# M150.net
KiCad netlist of a schematic drawn in Altium Designer
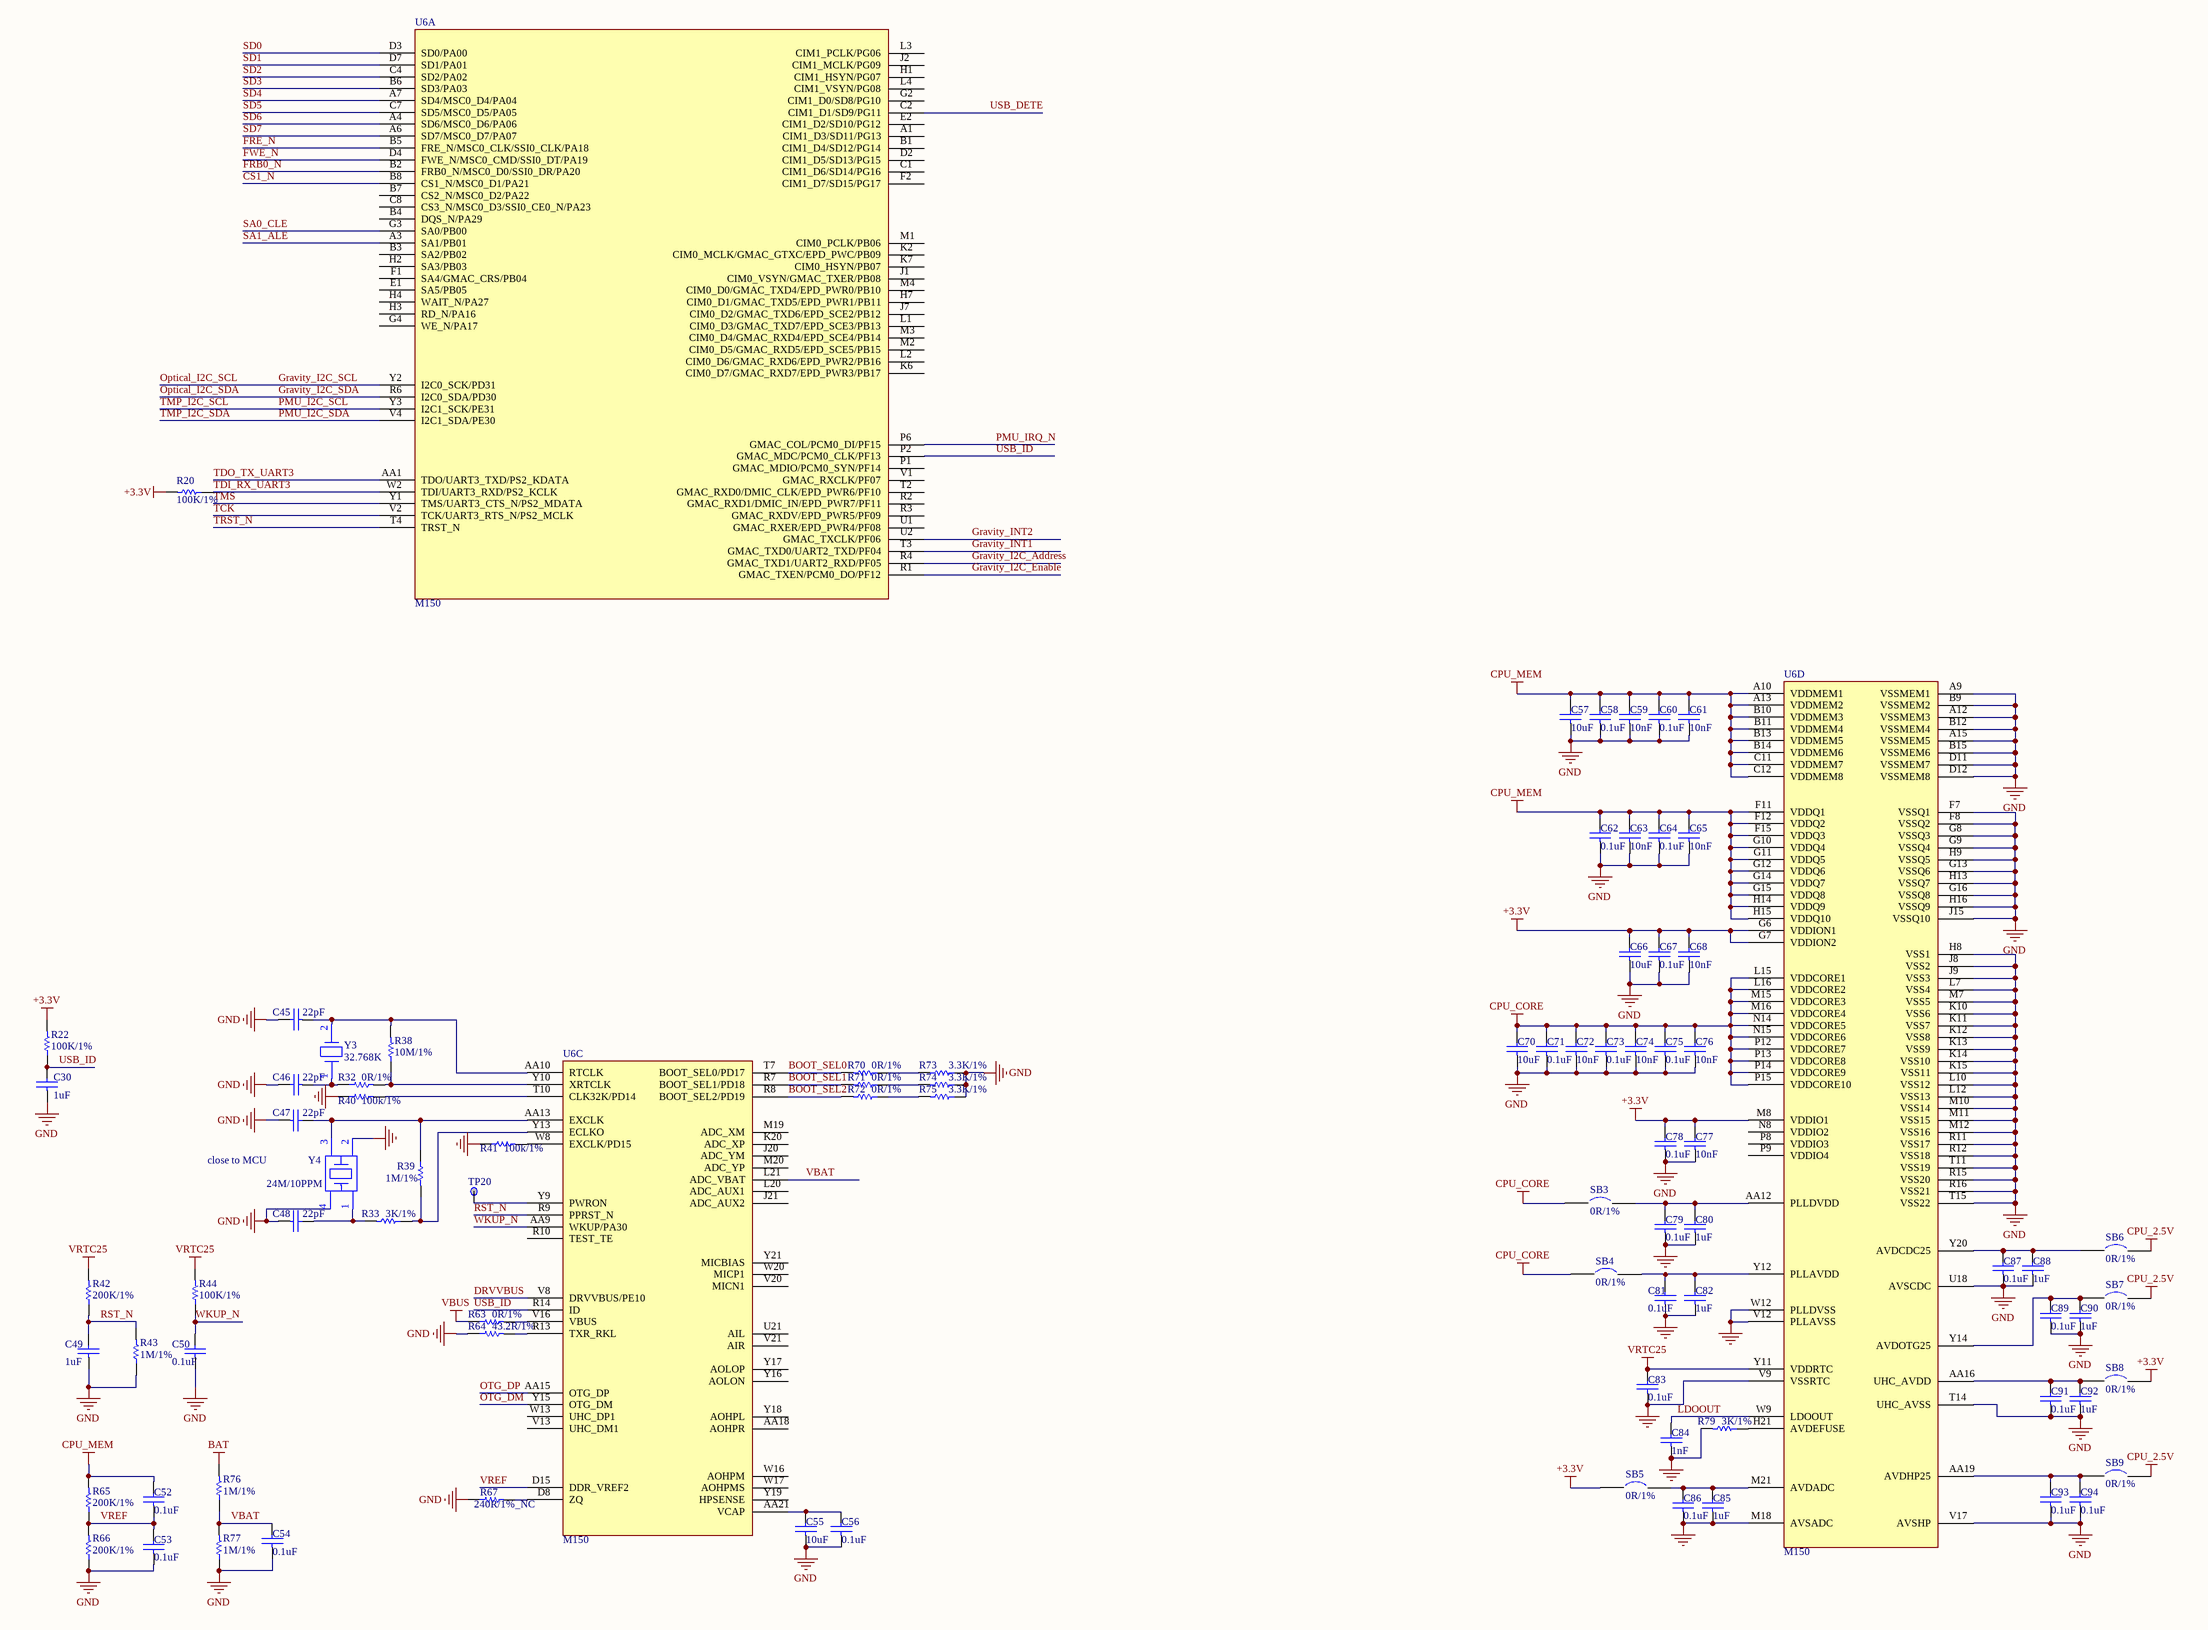
[diagram p0: M150.SchDoc]

(export (version "E")
  (design (tool "Eeschema 10.0.6"))
  (components
    (comp (ref "C30")
      (value "1uF")
      (footprint "0402C")
      (description "厂家：Murata，型号：GRM1555C1H120JA01D")
      (libsource (lib "Amber") (part "CAP"))
    )
    (comp (ref "C45")
      (value "22pF")
      (footprint "0402C")
      (description "Capacitor")
      (libsource (lib "*") (part "CAP"))
    )
    (comp (ref "C46")
      (value "22pF")
      (footprint "0402C")
      (description "Capacitor")
      (libsource (lib "*") (part "CAP"))
    )
    (comp (ref "C47")
      (value "22pF")
      (footprint "0402C")
      (description "厂家：Murata，型号：GRM1555C1H120JA01D")
      (libsource (lib "Amber") (part "CAP"))
    )
    (comp (ref "C48")
      (value "22pF")
      (footprint "0402C")
      (description "厂家：Murata，型号：GRM1555C1H120JA01D")
      (libsource (lib "Amber") (part "CAP"))
    )
    (comp (ref "C49")
      (value "1uF")
      (footprint "0402C")
      (description "厂家：Murata，型号：GRM1555C1H120JA01D")
      (libsource (lib "Amber") (part "CAP"))
    )
    (comp (ref "C50")
      (value "0.1uF")
      (footprint "0402C")
      (description "厂家：Murata，型号：GRM1555C1H120JA01D")
      (libsource (lib "Amber") (part "CAP"))
    )
    (comp (ref "C52")
      (value "0.1uF")
      (footprint "0402C")
      (description "厂家：Murata，型号：GRM1555C1H120JA01D")
      (libsource (lib "Amber") (part "CAP"))
    )
    (comp (ref "C53")
      (value "0.1uF")
      (footprint "0402C")
      (description "厂家：Murata，型号：GRM1555C1H120JA01D")
      (libsource (lib "Amber") (part "CAP"))
    )
    (comp (ref "C54")
      (value "0.1uF")
      (footprint "0402C")
      (description "厂家：Murata，型号：GRM1555C1H120JA01D")
      (libsource (lib "Amber") (part "CAP"))
    )
    (comp (ref "C55")
      (value "10uF")
      (footprint "0402C")
      (description "厂家：Murata，型号：GRM1555C1H120JA01D")
      (libsource (lib "Amber") (part "CAP"))
    )
    (comp (ref "C56")
      (value "0.1uF")
      (footprint "0402C")
      (description "厂家：Murata，型号：GRM1555C1H120JA01D")
      (libsource (lib "Amber") (part "CAP"))
    )
    (comp (ref "C57")
      (value "10uF")
      (footprint "0402C")
      (description "厂家：Murata，型号：GRM1555C1H120JA01D")
      (libsource (lib "Amber") (part "CAP"))
    )
    (comp (ref "C58")
      (value "0.1uF")
      (footprint "0402C")
      (description "厂家：Murata，型号：GRM1555C1H120JA01D")
      (libsource (lib "Amber") (part "CAP"))
    )
    (comp (ref "C59")
      (value "10nF")
      (footprint "0402C")
      (description "厂家：Murata，型号：GRM1555C1H120JA01D")
      (libsource (lib "Amber") (part "CAP"))
    )
    (comp (ref "C60")
      (value "0.1uF")
      (footprint "0402C")
      (description "厂家：Murata，型号：GRM1555C1H120JA01D")
      (libsource (lib "Amber") (part "CAP"))
    )
    (comp (ref "C61")
      (value "10nF")
      (footprint "0402C")
      (description "厂家：Murata，型号：GRM1555C1H120JA01D")
      (libsource (lib "Amber") (part "CAP"))
    )
    (comp (ref "C62")
      (value "0.1uF")
      (footprint "0402C")
      (description "厂家：Murata，型号：GRM1555C1H120JA01D")
      (libsource (lib "Amber") (part "CAP"))
    )
    (comp (ref "C63")
      (value "10nF")
      (footprint "0402C")
      (description "厂家：Murata，型号：GRM1555C1H120JA01D")
      (libsource (lib "Amber") (part "CAP"))
    )
    (comp (ref "C64")
      (value "0.1uF")
      (footprint "0402C")
      (description "厂家：Murata，型号：GRM1555C1H120JA01D")
      (libsource (lib "Amber") (part "CAP"))
    )
    (comp (ref "C65")
      (value "10nF")
      (footprint "0402C")
      (description "厂家：Murata，型号：GRM1555C1H120JA01D")
      (libsource (lib "Amber") (part "CAP"))
    )
    (comp (ref "C66")
      (value "10uF")
      (footprint "0402C")
      (description "厂家：Murata，型号：GRM1555C1H120JA01D")
      (libsource (lib "Amber") (part "CAP"))
    )
    (comp (ref "C67")
      (value "0.1uF")
      (footprint "0402C")
      (description "厂家：Murata，型号：GRM1555C1H120JA01D")
      (libsource (lib "Amber") (part "CAP"))
    )
    (comp (ref "C68")
      (value "10nF")
      (footprint "0402C")
      (description "厂家：Murata，型号：GRM1555C1H120JA01D")
      (libsource (lib "Amber") (part "CAP"))
    )
    (comp (ref "C70")
      (value "10uF")
      (footprint "0402C")
      (description "厂家：Murata，型号：GRM1555C1H120JA01D")
      (libsource (lib "Amber") (part "CAP"))
    )
    (comp (ref "C71")
      (value "0.1uF")
      (footprint "0402C")
      (description "厂家：Murata，型号：GRM1555C1H120JA01D")
      (libsource (lib "Amber") (part "CAP"))
    )
    (comp (ref "C72")
      (value "10nF")
      (footprint "0402C")
      (description "厂家：Murata，型号：GRM1555C1H120JA01D")
      (libsource (lib "Amber") (part "CAP"))
    )
    (comp (ref "C73")
      (value "0.1uF")
      (footprint "0402C")
      (description "厂家：Murata，型号：GRM1555C1H120JA01D")
      (libsource (lib "Amber") (part "CAP"))
    )
    (comp (ref "C74")
      (value "10nF")
      (footprint "0402C")
      (description "厂家：Murata，型号：GRM1555C1H120JA01D")
      (libsource (lib "Amber") (part "CAP"))
    )
    (comp (ref "C75")
      (value "0.1uF")
      (footprint "0402C")
      (description "厂家：Murata，型号：GRM1555C1H120JA01D")
      (libsource (lib "Amber") (part "CAP"))
    )
    (comp (ref "C76")
      (value "10nF")
      (footprint "0402C")
      (description "厂家：Murata，型号：GRM1555C1H120JA01D")
      (libsource (lib "Amber") (part "CAP"))
    )
    (comp (ref "C77")
      (value "10nF")
      (footprint "0402C")
      (description "厂家：Murata，型号：GRM1555C1H120JA01D")
      (libsource (lib "Amber") (part "CAP"))
    )
    (comp (ref "C78")
      (value "0.1uF")
      (footprint "0402C")
      (description "厂家：Murata，型号：GRM1555C1H120JA01D")
      (libsource (lib "Amber") (part "CAP"))
    )
    (comp (ref "C79")
      (value "0.1uF")
      (footprint "0402C")
      (description "厂家：Murata，型号：GRM1555C1H120JA01D")
      (libsource (lib "Amber") (part "CAP"))
    )
    (comp (ref "C80")
      (value "1uF")
      (footprint "0402C")
      (description "厂家：Murata，型号：GRM1555C1H120JA01D")
      (libsource (lib "Amber") (part "CAP"))
    )
    (comp (ref "C81")
      (value "0.1uF")
      (footprint "0402C")
      (description "厂家：Murata，型号：GRM1555C1H120JA01D")
      (libsource (lib "Amber") (part "CAP"))
    )
    (comp (ref "C82")
      (value "1uF")
      (footprint "0402C")
      (description "厂家：Murata，型号：GRM1555C1H120JA01D")
      (libsource (lib "Amber") (part "CAP"))
    )
    (comp (ref "C83")
      (value "0.1uF")
      (footprint "0402C")
      (description "厂家：Murata，型号：GRM1555C1H120JA01D")
      (libsource (lib "Amber") (part "CAP"))
    )
    (comp (ref "C84")
      (value "1nF")
      (footprint "0402C")
      (description "厂家：Murata，型号：GRM1555C1H120JA01D")
      (libsource (lib "Amber") (part "CAP"))
    )
    (comp (ref "C85")
      (value "1uF")
      (footprint "0402C")
      (description "厂家：Murata，型号：GRM1555C1H120JA01D")
      (libsource (lib "Amber") (part "CAP"))
    )
    (comp (ref "C86")
      (value "0.1uF")
      (footprint "0402C")
      (description "厂家：Murata，型号：GRM1555C1H120JA01D")
      (libsource (lib "Amber") (part "CAP"))
    )
    (comp (ref "C87")
      (value "0.1uF")
      (footprint "0402C")
      (description "厂家：Murata，型号：GRM1555C1H120JA01D")
      (libsource (lib "Amber") (part "CAP"))
    )
    (comp (ref "C88")
      (value "1uF")
      (footprint "0402C")
      (description "厂家：Murata，型号：GRM1555C1H120JA01D")
      (libsource (lib "Amber") (part "CAP"))
    )
    (comp (ref "C89")
      (value "0.1uF")
      (footprint "0402C")
      (description "厂家：Murata，型号：GRM1555C1H120JA01D")
      (libsource (lib "Amber") (part "CAP"))
    )
    (comp (ref "C90")
      (value "1uF")
      (footprint "0402C")
      (description "厂家：Murata，型号：GRM1555C1H120JA01D")
      (libsource (lib "Amber") (part "CAP"))
    )
    (comp (ref "C91")
      (value "0.1uF")
      (footprint "0402C")
      (description "厂家：Murata，型号：GRM1555C1H120JA01D")
      (libsource (lib "Amber") (part "CAP"))
    )
    (comp (ref "C92")
      (value "1uF")
      (footprint "0402C")
      (description "厂家：Murata，型号：GRM1555C1H120JA01D")
      (libsource (lib "Amber") (part "CAP"))
    )
    (comp (ref "C93")
      (value "0.1uF")
      (footprint "0402C")
      (description "厂家：Murata，型号：GRM1555C1H120JA01D")
      (libsource (lib "Amber") (part "CAP"))
    )
    (comp (ref "C94")
      (value "0.1uF")
      (footprint "0402C")
      (description "厂家：Murata，型号：GRM1555C1H120JA01D")
      (libsource (lib "Amber") (part "CAP"))
    )
    (comp (ref "R20")
      (value "100K/1%")
      (footprint "0603R")
      (description "Resistor")
      (fields (field (name "PUBLISHER") "Altium Limited"))
      (libsource (lib "Miscellaneous Devices") (part "Res1"))
    )
    (comp (ref "R22")
      (value "100K/1%")
      (footprint "0603R")
      (description "Resistor")
      (fields (field (name "PUBLISHER") "Altium Limited"))
      (libsource (lib "Miscellaneous Devices") (part "Res1"))
    )
    (comp (ref "R32")
      (value "0R/1%")
      (footprint "0603R")
      (description "Resistor")
      (fields (field (name "PUBLISHER") "Altium Limited"))
      (libsource (lib "Miscellaneous Devices") (part "Res1"))
    )
    (comp (ref "R33")
      (value "3K/1%")
      (footprint "0603R")
      (description "Resistor")
      (fields (field (name "PUBLISHER") "Altium Limited"))
      (libsource (lib "") (part "Res1_1"))
    )
    (comp (ref "R38")
      (value "10M/1%")
      (footprint "0603R")
      (description "Resistor")
      (fields (field (name "PUBLISHER") "Altium Limited"))
      (libsource (lib "Miscellaneous Devices") (part "Res1"))
    )
    (comp (ref "R39")
      (value "1M/1%")
      (footprint "0603R")
      (description "Resistor")
      (fields (field (name "PUBLISHER") "Altium Limited"))
      (libsource (lib "") (part "Res1_1"))
    )
    (comp (ref "R40")
      (value "100k/1%")
      (footprint "0603R")
      (description "Resistor")
      (fields (field (name "PUBLISHER") "Altium Limited"))
      (libsource (lib "Miscellaneous Devices") (part "Res1"))
    )
    (comp (ref "R41")
      (value "100k/1%")
      (footprint "0603R")
      (description "Resistor")
      (fields (field (name "PUBLISHER") "Altium Limited"))
      (libsource (lib "Miscellaneous Devices") (part "Res1"))
    )
    (comp (ref "R42")
      (value "200K/1%")
      (footprint "0603R")
      (description "Resistor")
      (fields (field (name "PUBLISHER") "Altium Limited"))
      (libsource (lib "Miscellaneous Devices") (part "Res1"))
    )
    (comp (ref "R43")
      (value "1M/1%")
      (footprint "0603R")
      (description "Resistor")
      (fields (field (name "PUBLISHER") "Altium Limited"))
      (libsource (lib "Miscellaneous Devices") (part "Res1"))
    )
    (comp (ref "R44")
      (value "100K/1%")
      (footprint "0603R")
      (description "Resistor")
      (fields (field (name "PUBLISHER") "Altium Limited"))
      (libsource (lib "Miscellaneous Devices") (part "Res1"))
    )
    (comp (ref "R63")
      (value "0R/1%")
      (footprint "0603R")
      (description "Resistor")
      (fields (field (name "PUBLISHER") "Altium Limited"))
      (libsource (lib "Miscellaneous Devices") (part "Res1"))
    )
    (comp (ref "R64")
      (value "43.2R/1%")
      (footprint "0603R")
      (description "Resistor")
      (fields (field (name "PUBLISHER") "Altium Limited"))
      (libsource (lib "Miscellaneous Devices") (part "Res1"))
    )
    (comp (ref "R65")
      (value "200K/1%")
      (footprint "0603R")
      (description "Resistor")
      (fields (field (name "PUBLISHER") "Altium Limited"))
      (libsource (lib "Miscellaneous Devices") (part "Res1"))
    )
    (comp (ref "R66")
      (value "200K/1%")
      (footprint "0603R")
      (description "Resistor")
      (fields (field (name "PUBLISHER") "Altium Limited"))
      (libsource (lib "Miscellaneous Devices") (part "Res1"))
    )
    (comp (ref "R67")
      (value "240R/1%_NC")
      (footprint "0603R")
      (description "Resistor")
      (fields (field (name "PUBLISHER") "Altium Limited"))
      (libsource (lib "Miscellaneous Devices") (part "Res1"))
    )
    (comp (ref "R70")
      (value "0R/1%")
      (footprint "0603R")
      (description "Resistor")
      (fields (field (name "PUBLISHER") "Altium Limited"))
      (libsource (lib "Miscellaneous Devices") (part "Res1"))
    )
    (comp (ref "R71")
      (value "0R/1%")
      (footprint "0603R")
      (description "Resistor")
      (fields (field (name "PUBLISHER") "Altium Limited"))
      (libsource (lib "Miscellaneous Devices") (part "Res1"))
    )
    (comp (ref "R72")
      (value "0R/1%")
      (footprint "0603R")
      (description "Resistor")
      (fields (field (name "PUBLISHER") "Altium Limited"))
      (libsource (lib "Miscellaneous Devices") (part "Res1"))
    )
    (comp (ref "R73")
      (value "3.3K/1%")
      (footprint "0603R")
      (description "Resistor")
      (fields (field (name "PUBLISHER") "Altium Limited"))
      (libsource (lib "Miscellaneous Devices") (part "Res1"))
    )
    (comp (ref "R74")
      (value "3.3K/1%")
      (footprint "0603R")
      (description "Resistor")
      (fields (field (name "PUBLISHER") "Altium Limited"))
      (libsource (lib "Miscellaneous Devices") (part "Res1"))
    )
    (comp (ref "R75")
      (value "3.3K/1%")
      (footprint "0603R")
      (description "Resistor")
      (fields (field (name "PUBLISHER") "Altium Limited"))
      (libsource (lib "Miscellaneous Devices") (part "Res1"))
    )
    (comp (ref "R76")
      (value "1M/1%")
      (footprint "0603R")
      (description "Resistor")
      (fields (field (name "PUBLISHER") "Altium Limited"))
      (libsource (lib "Miscellaneous Devices") (part "Res1"))
    )
    (comp (ref "R77")
      (value "1M/1%")
      (footprint "0603R")
      (description "Resistor")
      (fields (field (name "PUBLISHER") "Altium Limited"))
      (libsource (lib "Miscellaneous Devices") (part "Res1"))
    )
    (comp (ref "R79")
      (value "3K/1%")
      (footprint "0603R")
      (description "Resistor")
      (fields (field (name "PUBLISHER") "Altium Limited"))
      (libsource (lib "") (part "Res1_1"))
    )
    (comp (ref "SB3")
      (value "0R/1%")
      (footprint "SB_0603")
      (description "Circuit Breaker")
      (fields (field (name "PUBLISHER") "Altium Limited"))
      (libsource (lib "Miscellaneous Devices") (part "Circuit Breaker"))
    )
    (comp (ref "SB4")
      (value "0R/1%")
      (footprint "SB_0603")
      (description "Circuit Breaker")
      (fields (field (name "PUBLISHER") "Altium Limited"))
      (libsource (lib "Miscellaneous Devices") (part "Circuit Breaker"))
    )
    (comp (ref "SB5")
      (value "0R/1%")
      (footprint "SB_0603")
      (description "Circuit Breaker")
      (fields (field (name "PUBLISHER") "Altium Limited"))
      (libsource (lib "Miscellaneous Devices") (part "Circuit Breaker"))
    )
    (comp (ref "SB6")
      (value "0R/1%")
      (footprint "SB_0603")
      (description "Circuit Breaker")
      (fields (field (name "PUBLISHER") "Altium Limited"))
      (libsource (lib "Miscellaneous Devices") (part "Circuit Breaker"))
    )
    (comp (ref "SB7")
      (value "0R/1%")
      (footprint "SB_0603")
      (description "Circuit Breaker")
      (fields (field (name "PUBLISHER") "Altium Limited"))
      (libsource (lib "Miscellaneous Devices") (part "Circuit Breaker"))
    )
    (comp (ref "SB8")
      (value "0R/1%")
      (footprint "SB_0603")
      (description "Circuit Breaker")
      (fields (field (name "PUBLISHER") "Altium Limited"))
      (libsource (lib "Miscellaneous Devices") (part "Circuit Breaker"))
    )
    (comp (ref "SB9")
      (value "0R/1%")
      (footprint "SB_0603")
      (description "Circuit Breaker")
      (fields (field (name "PUBLISHER") "Altium Limited"))
      (libsource (lib "Miscellaneous Devices") (part "Circuit Breaker"))
    )
    (comp (ref "TP20") (value "TP") (footprint "TP_C40") (libsource (lib "Almos") (part "TP")))
    (comp (ref "U6") (value "M150") (footprint "Model Name") (libsource (lib "M150") (part "M150")))
    (comp (ref "Y3")
      (value "32.768K")
      (footprint "XTALSMD2-3215")
      (description "厂家：EPSON，型号：Q13FC1350000400")
      (libsource (lib "Amber") (part "CRYSTAL3"))
    )
    (comp (ref "Y4")
      (value "24M/10PPM")
      (footprint "XTALSMD2-2520")
      (description "厂家：EPSON，型号：Q24FA20H0004400")
      (libsource (lib "Amber_1") (part "CRYSTAL2"))
    )
  )
  (nets
    (net (code "1") (name "+3.3V") (class "Default")
      (node (ref "C66") (pin "2") (pinfunction "2_2") (pintype "passive"))
      (node (ref "C67") (pin "2") (pinfunction "2_2") (pintype "passive"))
      (node (ref "C68") (pin "2") (pinfunction "2_2") (pintype "passive"))
      (node (ref "C77") (pin "2") (pinfunction "2_2") (pintype "passive"))
      (node (ref "C78") (pin "2") (pinfunction "2_2") (pintype "passive"))
      (node (ref "R20") (pin "2") (pinfunction "2_2") (pintype "passive"))
      (node (ref "R22") (pin "2") (pinfunction "2_2") (pintype "passive"))
      (node (ref "SB5") (pin "1") (pinfunction "1_1") (pintype "passive"))
      (node (ref "SB8") (pin "2") (pinfunction "2_2") (pintype "passive"))
      (node (ref "U6") (pin "G6") (pinfunction "VDDION1_G6") (pintype "passive"))
      (node (ref "U6") (pin "G7") (pinfunction "VDDION2_G7") (pintype "passive"))
      (node (ref "U6") (pin "M8") (pinfunction "VDDIO1_M8") (pintype "passive"))
    )
    (net (code "2") (name "/BOOT_SEL0") (class "Default")
      (node (ref "R70") (pin "2") (pinfunction "2_2") (pintype "passive"))
      (node (ref "U6") (pin "T7") (pinfunction "BOOT_SEL0/PD17_T7") (pintype "passive"))
    )
    (net (code "3") (name "/BOOT_SEL1") (class "Default")
      (node (ref "R71") (pin "2") (pinfunction "2_2") (pintype "passive"))
      (node (ref "U6") (pin "R7") (pinfunction "BOOT_SEL1/PD18_R7") (pintype "passive"))
    )
    (net (code "4") (name "/BOOT_SEL2") (class "Default")
      (node (ref "R72") (pin "2") (pinfunction "2_2") (pintype "passive"))
      (node (ref "U6") (pin "R8") (pinfunction "BOOT_SEL2/PD19_R8") (pintype "passive"))
    )
    (net (code "5") (name "/CS1_N") (class "Default")
      (node (ref "U6") (pin "B8") (pinfunction "CS1_N/MSC0_D1/PA21_B8") (pintype "passive"))
    )
    (net (code "6") (name "/DRVVBUS") (class "Default")
      (node (ref "U6") (pin "V8") (pinfunction "DRVVBUS/PE10_V8") (pintype "passive"))
    )
    (net (code "7") (name "/FRB0_N") (class "Default")
      (node (ref "U6") (pin "B2") (pinfunction "FRB0_N/MSC0_D0/SSI0_DR/PA20_B2") (pintype "passive"))
    )
    (net (code "8") (name "/FRE_N") (class "Default")
      (node (ref "U6") (pin "B5") (pinfunction "FRE_N/MSC0_CLK/SSI0_CLK/PA18_B5") (pintype "passive"))
    )
    (net (code "9") (name "/FWE_N") (class "Default")
      (node (ref "U6") (pin "D4") (pinfunction "FWE_N/MSC0_CMD/SSI0_DT/PA19_D4") (pintype "passive"))
    )
    (net (code "10") (name "/Gravity_I2C_Address") (class "Default")
      (node (ref "U6") (pin "R4") (pinfunction "GMAC_TXD1/UART2_RXD/PF05_R4") (pintype "passive"))
    )
    (net (code "11") (name "/Gravity_I2C_Enable") (class "Default")
      (node (ref "U6") (pin "R1") (pinfunction "GMAC_TXEN/PCM0_DO/PF12_R1") (pintype "passive"))
    )
    (net (code "12") (name "/Gravity_I2C_SCL") (class "Default")
      (node (ref "U6") (pin "Y2") (pinfunction "I2C0_SCK/PD31_Y2") (pintype "passive"))
    )
    (net (code "13") (name "/Gravity_I2C_SDA") (class "Default")
      (node (ref "U6") (pin "R6") (pinfunction "I2C0_SDA/PD30_R6") (pintype "passive"))
    )
    (net (code "14") (name "/Gravity_INT1") (class "Default")
      (node (ref "U6") (pin "T3") (pinfunction "GMAC_TXD0/UART2_TXD/PF04_T3") (pintype "passive"))
    )
    (net (code "15") (name "/Gravity_INT2") (class "Default")
      (node (ref "U6") (pin "U2") (pinfunction "GMAC_TXCLK/PF06_U2") (pintype "passive"))
    )
    (net (code "16") (name "/LDOOUT") (class "Default")
      (node (ref "C84") (pin "2") (pinfunction "2_2") (pintype "passive"))
      (node (ref "U6") (pin "W9") (pinfunction "LDOOUT_W9") (pintype "passive"))
    )
    (net (code "17") (name "/OTG_DM") (class "Default")
      (node (ref "U6") (pin "Y15") (pinfunction "OTG_DM_Y15") (pintype "passive"))
    )
    (net (code "18") (name "/OTG_DP") (class "Default")
      (node (ref "U6") (pin "AA15") (pinfunction "OTG_DP_AA15") (pintype "passive"))
    )
    (net (code "19") (name "/PMU_I2C_SCL") (class "Default")
      (node (ref "U6") (pin "Y3") (pinfunction "I2C1_SCK/PE31_Y3") (pintype "passive"))
    )
    (net (code "20") (name "/PMU_I2C_SDA") (class "Default")
      (node (ref "U6") (pin "V4") (pinfunction "I2C1_SDA/PE30_V4") (pintype "passive"))
    )
    (net (code "21") (name "/PMU_IRQ_N") (class "Default")
      (node (ref "U6") (pin "P6") (pinfunction "GMAC_COL/PCM0_DI/PF15_P6") (pintype "passive"))
    )
    (net (code "22") (name "/RST_N") (class "Default")
      (node (ref "C49") (pin "2") (pinfunction "2_2") (pintype "passive"))
      (node (ref "R42") (pin "1") (pinfunction "1_1") (pintype "passive"))
      (node (ref "R43") (pin "2") (pinfunction "2_2") (pintype "passive"))
      (node (ref "U6") (pin "R9") (pinfunction "PPRST_N_R9") (pintype "passive"))
    )
    (net (code "23") (name "/SA0_CLE") (class "Default")
      (node (ref "U6") (pin "G3") (pinfunction "SA0/PB00_G3") (pintype "passive"))
    )
    (net (code "24") (name "/SA1_ALE") (class "Default")
      (node (ref "U6") (pin "A3") (pinfunction "SA1/PB01_A3") (pintype "passive"))
    )
    (net (code "25") (name "/SD0") (class "Default")
      (node (ref "U6") (pin "D3") (pinfunction "SD0/PA00_D3") (pintype "passive"))
    )
    (net (code "26") (name "/SD1") (class "Default")
      (node (ref "U6") (pin "D7") (pinfunction "SD1/PA01_D7") (pintype "passive"))
    )
    (net (code "27") (name "/SD2") (class "Default")
      (node (ref "U6") (pin "C4") (pinfunction "SD2/PA02_C4") (pintype "passive"))
    )
    (net (code "28") (name "/SD3") (class "Default")
      (node (ref "U6") (pin "B6") (pinfunction "SD3/PA03_B6") (pintype "passive"))
    )
    (net (code "29") (name "/SD4") (class "Default")
      (node (ref "U6") (pin "A7") (pinfunction "SD4/MSC0_D4/PA04_A7") (pintype "passive"))
    )
    (net (code "30") (name "/SD5") (class "Default")
      (node (ref "U6") (pin "C7") (pinfunction "SD5/MSC0_D5/PA05_C7") (pintype "passive"))
    )
    (net (code "31") (name "/SD6") (class "Default")
      (node (ref "U6") (pin "A4") (pinfunction "SD6/MSC0_D6/PA06_A4") (pintype "passive"))
    )
    (net (code "32") (name "/SD7") (class "Default")
      (node (ref "U6") (pin "A6") (pinfunction "SD7/MSC0_D7/PA07_A6") (pintype "passive"))
    )
    (net (code "33") (name "/TCK") (class "Default")
      (node (ref "U6") (pin "V2") (pinfunction "TCK/UART3_RTS_N/PS2_MCLK_V2") (pintype "passive"))
    )
    (net (code "34") (name "/TDI_RX_UART3") (class "Default")
      (node (ref "R20") (pin "1") (pinfunction "1_1") (pintype "passive"))
      (node (ref "U6") (pin "W2") (pinfunction "TDI/UART3_RXD/PS2_KCLK_W2") (pintype "passive"))
    )
    (net (code "35") (name "/TDO_TX_UART3") (class "Default")
      (node (ref "U6") (pin "AA1") (pinfunction "TDO/UART3_TXD/PS2_KDATA_AA1") (pintype "passive"))
    )
    (net (code "36") (name "/TMS") (class "Default")
      (node (ref "U6") (pin "Y1") (pinfunction "TMS/UART3_CTS_N/PS2_MDATA_Y1") (pintype "passive"))
    )
    (net (code "37") (name "/TRST_N") (class "Default")
      (node (ref "U6") (pin "T4") (pinfunction "TRST_N_T4") (pintype "passive"))
    )
    (net (code "38") (name "/USB_DETE") (class "Default")
      (node (ref "U6") (pin "C2") (pinfunction "CIM1_D1/SD9/PG11_C2") (pintype "passive"))
    )
    (net (code "39") (name "/USB_ID") (class "Default")
      (node (ref "C30") (pin "2") (pinfunction "2_2") (pintype "passive"))
      (node (ref "R22") (pin "1") (pinfunction "1_1") (pintype "passive"))
      (node (ref "U6") (pin "P2") (pinfunction "GMAC_MDC/PCM0_CLK/PF13_P2") (pintype "passive"))
      (node (ref "U6") (pin "R14") (pinfunction "ID_R14") (pintype "passive"))
    )
    (net (code "40") (name "/VBAT") (class "Default")
      (node (ref "C54") (pin "2") (pinfunction "2_2") (pintype "passive"))
      (node (ref "R76") (pin "1") (pinfunction "1_1") (pintype "passive"))
      (node (ref "R77") (pin "2") (pinfunction "2_2") (pintype "passive"))
      (node (ref "U6") (pin "L21") (pinfunction "ADC_VBAT_L21") (pintype "passive"))
    )
    (net (code "41") (name "/VREF") (class "Default")
      (node (ref "C52") (pin "1") (pinfunction "1_1") (pintype "passive"))
      (node (ref "C53") (pin "2") (pinfunction "2_2") (pintype "passive"))
      (node (ref "R65") (pin "1") (pinfunction "1_1") (pintype "passive"))
      (node (ref "R66") (pin "2") (pinfunction "2_2") (pintype "passive"))
      (node (ref "U6") (pin "D15") (pinfunction "DDR_VREF2_D15") (pintype "passive"))
    )
    (net (code "42") (name "/WKUP_N") (class "Default")
      (node (ref "C50") (pin "2") (pinfunction "2_2") (pintype "passive"))
      (node (ref "R44") (pin "1") (pinfunction "1_1") (pintype "passive"))
      (node (ref "U6") (pin "AA9") (pinfunction "WKUP/PA30_AA9") (pintype "passive"))
    )
    (net (code "43") (name "BAT") (class "Default")
      (node (ref "R76") (pin "2") (pinfunction "2_2") (pintype "passive"))
    )
    (net (code "44") (name "CPU_2.5V") (class "Default")
      (node (ref "SB6") (pin "2") (pinfunction "2_2") (pintype "passive"))
      (node (ref "SB7") (pin "2") (pinfunction "2_2") (pintype "passive"))
      (node (ref "SB9") (pin "2") (pinfunction "2_2") (pintype "passive"))
    )
    (net (code "45") (name "CPU_CORE") (class "Default")
      (node (ref "C70") (pin "2") (pinfunction "2_2") (pintype "passive"))
      (node (ref "C71") (pin "2") (pinfunction "2_2") (pintype "passive"))
      (node (ref "C72") (pin "2") (pinfunction "2_2") (pintype "passive"))
      (node (ref "C73") (pin "2") (pinfunction "2_2") (pintype "passive"))
      (node (ref "C74") (pin "2") (pinfunction "2_2") (pintype "passive"))
      (node (ref "C75") (pin "2") (pinfunction "2_2") (pintype "passive"))
      (node (ref "C76") (pin "2") (pinfunction "2_2") (pintype "passive"))
      (node (ref "SB3") (pin "1") (pinfunction "1_1") (pintype "passive"))
      (node (ref "SB4") (pin "1") (pinfunction "1_1") (pintype "passive"))
      (node (ref "U6") (pin "L15") (pinfunction "VDDCORE1_L15") (pintype "passive"))
      (node (ref "U6") (pin "L16") (pinfunction "VDDCORE2_L16") (pintype "passive"))
      (node (ref "U6") (pin "M15") (pinfunction "VDDCORE3_M15") (pintype "passive"))
      (node (ref "U6") (pin "M16") (pinfunction "VDDCORE4_M16") (pintype "passive"))
      (node (ref "U6") (pin "N14") (pinfunction "VDDCORE5_N14") (pintype "passive"))
      (node (ref "U6") (pin "N15") (pinfunction "VDDCORE6_N15") (pintype "passive"))
      (node (ref "U6") (pin "P12") (pinfunction "VDDCORE7_P12") (pintype "passive"))
      (node (ref "U6") (pin "P13") (pinfunction "VDDCORE8_P13") (pintype "passive"))
      (node (ref "U6") (pin "P14") (pinfunction "VDDCORE9_P14") (pintype "passive"))
      (node (ref "U6") (pin "P15") (pinfunction "VDDCORE10_P15") (pintype "passive"))
    )
    (net (code "46") (name "CPU_MEM") (class "Default")
      (node (ref "C52") (pin "2") (pinfunction "2_2") (pintype "passive"))
      (node (ref "C57") (pin "2") (pinfunction "2_2") (pintype "passive"))
      (node (ref "C58") (pin "2") (pinfunction "2_2") (pintype "passive"))
      (node (ref "C59") (pin "2") (pinfunction "2_2") (pintype "passive"))
      (node (ref "C60") (pin "2") (pinfunction "2_2") (pintype "passive"))
      (node (ref "C61") (pin "2") (pinfunction "2_2") (pintype "passive"))
      (node (ref "C62") (pin "2") (pinfunction "2_2") (pintype "passive"))
      (node (ref "C63") (pin "2") (pinfunction "2_2") (pintype "passive"))
      (node (ref "C64") (pin "2") (pinfunction "2_2") (pintype "passive"))
      (node (ref "C65") (pin "2") (pinfunction "2_2") (pintype "passive"))
      (node (ref "R65") (pin "2") (pinfunction "2_2") (pintype "passive"))
      (node (ref "U6") (pin "A10") (pinfunction "VDDMEM1_A10") (pintype "passive"))
      (node (ref "U6") (pin "A13") (pinfunction "VDDMEM2_A13") (pintype "passive"))
      (node (ref "U6") (pin "B10") (pinfunction "VDDMEM3_B10") (pintype "passive"))
      (node (ref "U6") (pin "B11") (pinfunction "VDDMEM4_B11") (pintype "passive"))
      (node (ref "U6") (pin "B13") (pinfunction "VDDMEM5_B13") (pintype "passive"))
      (node (ref "U6") (pin "B14") (pinfunction "VDDMEM6_B14") (pintype "passive"))
      (node (ref "U6") (pin "C11") (pinfunction "VDDMEM7_C11") (pintype "passive"))
      (node (ref "U6") (pin "C12") (pinfunction "VDDMEM8_C12") (pintype "passive"))
      (node (ref "U6") (pin "F11") (pinfunction "VDDQ1_F11") (pintype "passive"))
      (node (ref "U6") (pin "F12") (pinfunction "VDDQ2_F12") (pintype "passive"))
      (node (ref "U6") (pin "F15") (pinfunction "VDDQ3_F15") (pintype "passive"))
      (node (ref "U6") (pin "G10") (pinfunction "VDDQ4_G10") (pintype "passive"))
      (node (ref "U6") (pin "G11") (pinfunction "VDDQ5_G11") (pintype "passive"))
      (node (ref "U6") (pin "G12") (pinfunction "VDDQ6_G12") (pintype "passive"))
      (node (ref "U6") (pin "G14") (pinfunction "VDDQ7_G14") (pintype "passive"))
      (node (ref "U6") (pin "G15") (pinfunction "VDDQ8_G15") (pintype "passive"))
      (node (ref "U6") (pin "H14") (pinfunction "VDDQ9_H14") (pintype "passive"))
      (node (ref "U6") (pin "H15") (pinfunction "VDDQ10_H15") (pintype "passive"))
    )
    (net (code "47") (name "GND") (class "Default")
      (node (ref "C30") (pin "1") (pinfunction "1_1") (pintype "passive"))
      (node (ref "C45") (pin "2") (pinfunction "2_2") (pintype "passive"))
      (node (ref "C46") (pin "2") (pinfunction "2_2") (pintype "passive"))
      (node (ref "C47") (pin "1") (pinfunction "1_1") (pintype "passive"))
      (node (ref "C48") (pin "1") (pinfunction "1_1") (pintype "passive"))
      (node (ref "C49") (pin "1") (pinfunction "1_1") (pintype "passive"))
      (node (ref "C50") (pin "1") (pinfunction "1_1") (pintype "passive"))
      (node (ref "C53") (pin "1") (pinfunction "1_1") (pintype "passive"))
      (node (ref "C54") (pin "1") (pinfunction "1_1") (pintype "passive"))
      (node (ref "C55") (pin "1") (pinfunction "1_1") (pintype "passive"))
      (node (ref "C56") (pin "1") (pinfunction "1_1") (pintype "passive"))
      (node (ref "C57") (pin "1") (pinfunction "1_1") (pintype "passive"))
      (node (ref "C58") (pin "1") (pinfunction "1_1") (pintype "passive"))
      (node (ref "C59") (pin "1") (pinfunction "1_1") (pintype "passive"))
      (node (ref "C60") (pin "1") (pinfunction "1_1") (pintype "passive"))
      (node (ref "C61") (pin "1") (pinfunction "1_1") (pintype "passive"))
      (node (ref "C62") (pin "1") (pinfunction "1_1") (pintype "passive"))
      (node (ref "C63") (pin "1") (pinfunction "1_1") (pintype "passive"))
      (node (ref "C64") (pin "1") (pinfunction "1_1") (pintype "passive"))
      (node (ref "C65") (pin "1") (pinfunction "1_1") (pintype "passive"))
      (node (ref "C66") (pin "1") (pinfunction "1_1") (pintype "passive"))
      (node (ref "C67") (pin "1") (pinfunction "1_1") (pintype "passive"))
      (node (ref "C68") (pin "1") (pinfunction "1_1") (pintype "passive"))
      (node (ref "C70") (pin "1") (pinfunction "1_1") (pintype "passive"))
      (node (ref "C71") (pin "1") (pinfunction "1_1") (pintype "passive"))
      (node (ref "C72") (pin "1") (pinfunction "1_1") (pintype "passive"))
      (node (ref "C73") (pin "1") (pinfunction "1_1") (pintype "passive"))
      (node (ref "C74") (pin "1") (pinfunction "1_1") (pintype "passive"))
      (node (ref "C75") (pin "1") (pinfunction "1_1") (pintype "passive"))
      (node (ref "C76") (pin "1") (pinfunction "1_1") (pintype "passive"))
      (node (ref "C77") (pin "1") (pinfunction "1_1") (pintype "passive"))
      (node (ref "C78") (pin "1") (pinfunction "1_1") (pintype "passive"))
      (node (ref "C79") (pin "1") (pinfunction "1_1") (pintype "passive"))
      (node (ref "C80") (pin "1") (pinfunction "1_1") (pintype "passive"))
      (node (ref "C81") (pin "1") (pinfunction "1_1") (pintype "passive"))
      (node (ref "C82") (pin "1") (pinfunction "1_1") (pintype "passive"))
      (node (ref "C83") (pin "1") (pinfunction "1_1") (pintype "passive"))
      (node (ref "C84") (pin "1") (pinfunction "1_1") (pintype "passive"))
      (node (ref "C85") (pin "1") (pinfunction "1_1") (pintype "passive"))
      (node (ref "C86") (pin "1") (pinfunction "1_1") (pintype "passive"))
      (node (ref "C87") (pin "1") (pinfunction "1_1") (pintype "passive"))
      (node (ref "C88") (pin "1") (pinfunction "1_1") (pintype "passive"))
      (node (ref "C89") (pin "1") (pinfunction "1_1") (pintype "passive"))
      (node (ref "C90") (pin "1") (pinfunction "1_1") (pintype "passive"))
      (node (ref "C91") (pin "1") (pinfunction "1_1") (pintype "passive"))
      (node (ref "C92") (pin "1") (pinfunction "1_1") (pintype "passive"))
      (node (ref "C93") (pin "1") (pinfunction "1_1") (pintype "passive"))
      (node (ref "C94") (pin "1") (pinfunction "1_1") (pintype "passive"))
      (node (ref "R40") (pin "1") (pinfunction "1_1") (pintype "passive"))
      (node (ref "R41") (pin "1") (pinfunction "1_1") (pintype "passive"))
      (node (ref "R43") (pin "1") (pinfunction "1_1") (pintype "passive"))
      (node (ref "R64") (pin "1") (pinfunction "1_1") (pintype "passive"))
      (node (ref "R66") (pin "1") (pinfunction "1_1") (pintype "passive"))
      (node (ref "R67") (pin "1") (pinfunction "1_1") (pintype "passive"))
      (node (ref "R73") (pin "1") (pinfunction "1_1") (pintype "passive"))
      (node (ref "R74") (pin "1") (pinfunction "1_1") (pintype "passive"))
      (node (ref "R75") (pin "1") (pinfunction "1_1") (pintype "passive"))
      (node (ref "R77") (pin "1") (pinfunction "1_1") (pintype "passive"))
      (node (ref "R79") (pin "2") (pinfunction "2_2") (pintype "passive"))
      (node (ref "U6") (pin "A12") (pinfunction "VSSMEM3_A12") (pintype "passive"))
      (node (ref "U6") (pin "A15") (pinfunction "VSSMEM5_A15") (pintype "passive"))
      (node (ref "U6") (pin "A9") (pinfunction "VSSMEM1_A9") (pintype "passive"))
      (node (ref "U6") (pin "B12") (pinfunction "VSSMEM4_B12") (pintype "passive"))
      (node (ref "U6") (pin "B15") (pinfunction "VSSMEM6_B15") (pintype "passive"))
      (node (ref "U6") (pin "B9") (pinfunction "VSSMEM2_B9") (pintype "passive"))
      (node (ref "U6") (pin "D11") (pinfunction "VSSMEM7_D11") (pintype "passive"))
      (node (ref "U6") (pin "D12") (pinfunction "VSSMEM8_D12") (pintype "passive"))
      (node (ref "U6") (pin "F7") (pinfunction "VSSQ1_F7") (pintype "passive"))
      (node (ref "U6") (pin "F8") (pinfunction "VSSQ2_F8") (pintype "passive"))
      (node (ref "U6") (pin "G13") (pinfunction "VSSQ6_G13") (pintype "passive"))
      (node (ref "U6") (pin "G16") (pinfunction "VSSQ8_G16") (pintype "passive"))
      (node (ref "U6") (pin "G8") (pinfunction "VSSQ3_G8") (pintype "passive"))
      (node (ref "U6") (pin "G9") (pinfunction "VSSQ4_G9") (pintype "passive"))
      (node (ref "U6") (pin "H13") (pinfunction "VSSQ7_H13") (pintype "passive"))
      (node (ref "U6") (pin "H16") (pinfunction "VSSQ9_H16") (pintype "passive"))
      (node (ref "U6") (pin "H8") (pinfunction "VSS1_H8") (pintype "passive"))
      (node (ref "U6") (pin "H9") (pinfunction "VSSQ5_H9") (pintype "passive"))
      (node (ref "U6") (pin "J15") (pinfunction "VSSQ10_J15") (pintype "passive"))
      (node (ref "U6") (pin "J8") (pinfunction "VSS2_J8") (pintype "passive"))
      (node (ref "U6") (pin "J9") (pinfunction "VSS3_J9") (pintype "passive"))
      (node (ref "U6") (pin "K10") (pinfunction "VSS6_K10") (pintype "passive"))
      (node (ref "U6") (pin "K11") (pinfunction "VSS7_K11") (pintype "passive"))
      (node (ref "U6") (pin "K12") (pinfunction "VSS8_K12") (pintype "passive"))
      (node (ref "U6") (pin "K13") (pinfunction "VSS9_K13") (pintype "passive"))
      (node (ref "U6") (pin "K14") (pinfunction "VSS10_K14") (pintype "passive"))
      (node (ref "U6") (pin "K15") (pinfunction "VSS11_K15") (pintype "passive"))
      (node (ref "U6") (pin "L10") (pinfunction "VSS12_L10") (pintype "passive"))
      (node (ref "U6") (pin "L12") (pinfunction "VSS13_L12") (pintype "passive"))
      (node (ref "U6") (pin "L7") (pinfunction "VSS4_L7") (pintype "passive"))
      (node (ref "U6") (pin "M10") (pinfunction "VSS14_M10") (pintype "passive"))
      (node (ref "U6") (pin "M11") (pinfunction "VSS15_M11") (pintype "passive"))
      (node (ref "U6") (pin "M12") (pinfunction "VSS16_M12") (pintype "passive"))
      (node (ref "U6") (pin "M18") (pinfunction "AVSADC_M18") (pintype "passive"))
      (node (ref "U6") (pin "M7") (pinfunction "VSS5_M7") (pintype "passive"))
      (node (ref "U6") (pin "R11") (pinfunction "VSS17_R11") (pintype "passive"))
      (node (ref "U6") (pin "R12") (pinfunction "VSS18_R12") (pintype "passive"))
      (node (ref "U6") (pin "R15") (pinfunction "VSS20_R15") (pintype "passive"))
      (node (ref "U6") (pin "R16") (pinfunction "VSS21_R16") (pintype "passive"))
      (node (ref "U6") (pin "T11") (pinfunction "VSS19_T11") (pintype "passive"))
      (node (ref "U6") (pin "T14") (pinfunction "UHC_AVSS_T14") (pintype "passive"))
      (node (ref "U6") (pin "T15") (pinfunction "VSS22_T15") (pintype "passive"))
      (node (ref "U6") (pin "U18") (pinfunction "AVSCDC_U18") (pintype "passive"))
      (node (ref "U6") (pin "V12") (pinfunction "PLLAVSS_V12") (pintype "passive"))
      (node (ref "U6") (pin "V17") (pinfunction "AVSHP_V17") (pintype "passive"))
      (node (ref "U6") (pin "V9") (pinfunction "VSSRTC_V9") (pintype "passive"))
      (node (ref "U6") (pin "W12") (pinfunction "PLLDVSS_W12") (pintype "passive"))
      (node (ref "Y4") (pin "2") (pinfunction "2_2") (pintype "passive"))
      (node (ref "Y4") (pin "4") (pinfunction "4_4") (pintype "passive"))
    )
    (net (code "48") (name "Net-(C46-Pad1)") (class "Default")
      (node (ref "C46") (pin "1") (pinfunction "1_1") (pintype "passive"))
      (node (ref "R32") (pin "1") (pinfunction "1_1") (pintype "passive"))
      (node (ref "Y3") (pin "1") (pinfunction "1_1") (pintype "passive"))
    )
    (net (code "49") (name "Net-(C48-Pad2)") (class "Default")
      (node (ref "C48") (pin "2") (pinfunction "2_2") (pintype "passive"))
      (node (ref "R33") (pin "2") (pinfunction "2_2") (pintype "passive"))
      (node (ref "Y4") (pin "1") (pinfunction "1_1") (pintype "passive"))
    )
    (net (code "50") (name "Net-(R70-Pad1)") (class "Default")
      (node (ref "R70") (pin "1") (pinfunction "1_1") (pintype "passive"))
      (node (ref "R73") (pin "2") (pinfunction "2_2") (pintype "passive"))
    )
    (net (code "51") (name "Net-(R71-Pad1)") (class "Default")
      (node (ref "R71") (pin "1") (pinfunction "1_1") (pintype "passive"))
      (node (ref "R74") (pin "2") (pinfunction "2_2") (pintype "passive"))
    )
    (net (code "52") (name "Net-(R72-Pad1)") (class "Default")
      (node (ref "R72") (pin "1") (pinfunction "1_1") (pintype "passive"))
      (node (ref "R75") (pin "2") (pinfunction "2_2") (pintype "passive"))
    )
    (net (code "53") (name "Net-(U6C-CLK32K{slash}PD14)") (class "Default")
      (node (ref "R40") (pin "2") (pinfunction "2_2") (pintype "passive"))
      (node (ref "U6") (pin "T10") (pinfunction "CLK32K/PD14_T10") (pintype "passive"))
    )
    (net (code "54") (name "Net-(U6C-ECLKO)") (class "Default")
      (node (ref "R33") (pin "1") (pinfunction "1_1") (pintype "passive"))
      (node (ref "R39") (pin "2") (pinfunction "2_2") (pintype "passive"))
      (node (ref "U6") (pin "Y13") (pinfunction "ECLKO_Y13") (pintype "passive"))
    )
    (net (code "55") (name "Net-(U6C-EXCLK)") (class "Default")
      (node (ref "C47") (pin "2") (pinfunction "2_2") (pintype "passive"))
      (node (ref "R39") (pin "1") (pinfunction "1_1") (pintype "passive"))
      (node (ref "U6") (pin "AA13") (pinfunction "EXCLK_AA13") (pintype "passive"))
      (node (ref "Y4") (pin "3") (pinfunction "3_3") (pintype "passive"))
    )
    (net (code "56") (name "Net-(U6C-EXCLK{slash}PD15)") (class "Default")
      (node (ref "R41") (pin "2") (pinfunction "2_2") (pintype "passive"))
      (node (ref "U6") (pin "W8") (pinfunction "EXCLK/PD15_W8") (pintype "passive"))
    )
    (net (code "57") (name "Net-(U6C-PWRON)") (class "Default")
      (node (ref "TP20") (pin "1") (pinfunction "1_1") (pintype "passive"))
      (node (ref "U6") (pin "Y9") (pinfunction "PWRON_Y9") (pintype "passive"))
    )
    (net (code "58") (name "Net-(U6C-RTCLK)") (class "Default")
      (node (ref "C45") (pin "1") (pinfunction "1_1") (pintype "passive"))
      (node (ref "R38") (pin "2") (pinfunction "2_2") (pintype "passive"))
      (node (ref "U6") (pin "AA10") (pinfunction "RTCLK_AA10") (pintype "passive"))
      (node (ref "Y3") (pin "2") (pinfunction "2_2") (pintype "passive"))
    )
    (net (code "59") (name "Net-(U6C-TXR_RKL)") (class "Default")
      (node (ref "R64") (pin "2") (pinfunction "2_2") (pintype "passive"))
      (node (ref "U6") (pin "R13") (pinfunction "TXR_RKL_R13") (pintype "passive"))
    )
    (net (code "60") (name "Net-(U6C-VBUS)") (class "Default")
      (node (ref "R63") (pin "2") (pinfunction "2_2") (pintype "passive"))
      (node (ref "U6") (pin "V16") (pinfunction "VBUS_V16") (pintype "passive"))
    )
    (net (code "61") (name "Net-(U6C-VCAP)") (class "Default")
      (node (ref "C55") (pin "2") (pinfunction "2_2") (pintype "passive"))
      (node (ref "C56") (pin "2") (pinfunction "2_2") (pintype "passive"))
      (node (ref "U6") (pin "AA21") (pinfunction "VCAP_AA21") (pintype "passive"))
    )
    (net (code "62") (name "Net-(U6C-XRTCLK)") (class "Default")
      (node (ref "R32") (pin "2") (pinfunction "2_2") (pintype "passive"))
      (node (ref "R38") (pin "1") (pinfunction "1_1") (pintype "passive"))
      (node (ref "U6") (pin "Y10") (pinfunction "XRTCLK_Y10") (pintype "passive"))
    )
    (net (code "63") (name "Net-(U6C-ZQ)") (class "Default")
      (node (ref "R67") (pin "2") (pinfunction "2_2") (pintype "passive"))
      (node (ref "U6") (pin "D8") (pinfunction "ZQ_D8") (pintype "passive"))
    )
    (net (code "64") (name "Net-(U6D-AVDADC)") (class "Default")
      (node (ref "C85") (pin "2") (pinfunction "2_2") (pintype "passive"))
      (node (ref "C86") (pin "2") (pinfunction "2_2") (pintype "passive"))
      (node (ref "SB5") (pin "2") (pinfunction "2_2") (pintype "passive"))
      (node (ref "U6") (pin "M21") (pinfunction "AVDADC_M21") (pintype "passive"))
    )
    (net (code "65") (name "Net-(U6D-AVDCDC25)") (class "Default")
      (node (ref "C87") (pin "2") (pinfunction "2_2") (pintype "passive"))
      (node (ref "C88") (pin "2") (pinfunction "2_2") (pintype "passive"))
      (node (ref "SB6") (pin "1") (pinfunction "1_1") (pintype "passive"))
      (node (ref "U6") (pin "Y20") (pinfunction "AVDCDC25_Y20") (pintype "passive"))
    )
    (net (code "66") (name "Net-(U6D-AVDEFUSE)") (class "Default")
      (node (ref "R79") (pin "1") (pinfunction "1_1") (pintype "passive"))
      (node (ref "U6") (pin "H21") (pinfunction "AVDEFUSE_H21") (pintype "passive"))
    )
    (net (code "67") (name "Net-(U6D-AVDHP25)") (class "Default")
      (node (ref "C93") (pin "2") (pinfunction "2_2") (pintype "passive"))
      (node (ref "C94") (pin "2") (pinfunction "2_2") (pintype "passive"))
      (node (ref "SB9") (pin "1") (pinfunction "1_1") (pintype "passive"))
      (node (ref "U6") (pin "AA19") (pinfunction "AVDHP25_AA19") (pintype "passive"))
    )
    (net (code "68") (name "Net-(U6D-AVDOTG25)") (class "Default")
      (node (ref "C89") (pin "2") (pinfunction "2_2") (pintype "passive"))
      (node (ref "C90") (pin "2") (pinfunction "2_2") (pintype "passive"))
      (node (ref "SB7") (pin "1") (pinfunction "1_1") (pintype "passive"))
      (node (ref "U6") (pin "Y14") (pinfunction "AVDOTG25_Y14") (pintype "passive"))
    )
    (net (code "69") (name "Net-(U6D-PLLAVDD)") (class "Default")
      (node (ref "C81") (pin "2") (pinfunction "2_2") (pintype "passive"))
      (node (ref "C82") (pin "2") (pinfunction "2_2") (pintype "passive"))
      (node (ref "SB4") (pin "2") (pinfunction "2_2") (pintype "passive"))
      (node (ref "U6") (pin "Y12") (pinfunction "PLLAVDD_Y12") (pintype "passive"))
    )
    (net (code "70") (name "Net-(U6D-PLLDVDD)") (class "Default")
      (node (ref "C79") (pin "2") (pinfunction "2_2") (pintype "passive"))
      (node (ref "C80") (pin "2") (pinfunction "2_2") (pintype "passive"))
      (node (ref "SB3") (pin "2") (pinfunction "2_2") (pintype "passive"))
      (node (ref "U6") (pin "AA12") (pinfunction "PLLDVDD_AA12") (pintype "passive"))
    )
    (net (code "71") (name "Net-(U6D-UHC_AVDD)") (class "Default")
      (node (ref "C91") (pin "2") (pinfunction "2_2") (pintype "passive"))
      (node (ref "C92") (pin "2") (pinfunction "2_2") (pintype "passive"))
      (node (ref "SB8") (pin "1") (pinfunction "1_1") (pintype "passive"))
      (node (ref "U6") (pin "AA16") (pinfunction "UHC_AVDD_AA16") (pintype "passive"))
    )
    (net (code "72") (name "VBUS") (class "Default")
      (node (ref "R63") (pin "1") (pinfunction "1_1") (pintype "passive"))
    )
    (net (code "73") (name "VRTC25") (class "Default")
      (node (ref "C83") (pin "2") (pinfunction "2_2") (pintype "passive"))
      (node (ref "R42") (pin "2") (pinfunction "2_2") (pintype "passive"))
      (node (ref "R44") (pin "2") (pinfunction "2_2") (pintype "passive"))
      (node (ref "U6") (pin "Y11") (pinfunction "VDDRTC_Y11") (pintype "passive"))
    )
    (net (code "74") (name "unconnected-(U6A-CIM0_D0{slash}GMAC_TXD4{slash}EPD_PWR0{slash}PB10-PadM4)") (class "Default")
      (node (ref "U6") (pin "M4") (pinfunction "CIM0_D0/GMAC_TXD4/EPD_PWR0/PB10_M4") (pintype "passive"))
    )
    (net (code "75") (name "unconnected-(U6A-CIM0_D1{slash}GMAC_TXD5{slash}EPD_PWR1{slash}PB11-PadH7)") (class "Default")
      (node (ref "U6") (pin "H7") (pinfunction "CIM0_D1/GMAC_TXD5/EPD_PWR1/PB11_H7") (pintype "passive"))
    )
    (net (code "76") (name "unconnected-(U6A-CIM0_D2{slash}GMAC_TXD6{slash}EPD_SCE2{slash}PB12-PadJ7)") (class "Default")
      (node (ref "U6") (pin "J7") (pinfunction "CIM0_D2/GMAC_TXD6/EPD_SCE2/PB12_J7") (pintype "passive"))
    )
    (net (code "77") (name "unconnected-(U6A-CIM0_D3{slash}GMAC_TXD7{slash}EPD_SCE3{slash}PB13-PadL1)") (class "Default")
      (node (ref "U6") (pin "L1") (pinfunction "CIM0_D3/GMAC_TXD7/EPD_SCE3/PB13_L1") (pintype "passive"))
    )
    (net (code "78") (name "unconnected-(U6A-CIM0_D4{slash}GMAC_RXD4{slash}EPD_SCE4{slash}PB14-PadM3)") (class "Default")
      (node (ref "U6") (pin "M3") (pinfunction "CIM0_D4/GMAC_RXD4/EPD_SCE4/PB14_M3") (pintype "passive"))
    )
    (net (code "79") (name "unconnected-(U6A-CIM0_D5{slash}GMAC_RXD5{slash}EPD_SCE5{slash}PB15-PadM2)") (class "Default")
      (node (ref "U6") (pin "M2") (pinfunction "CIM0_D5/GMAC_RXD5/EPD_SCE5/PB15_M2") (pintype "passive"))
    )
    (net (code "80") (name "unconnected-(U6A-CIM0_D6{slash}GMAC_RXD6{slash}EPD_PWR2{slash}PB16-PadL2)") (class "Default")
      (node (ref "U6") (pin "L2") (pinfunction "CIM0_D6/GMAC_RXD6/EPD_PWR2/PB16_L2") (pintype "passive"))
    )
    (net (code "81") (name "unconnected-(U6A-CIM0_D7{slash}GMAC_RXD7{slash}EPD_PWR3{slash}PB17-PadK6)") (class "Default")
      (node (ref "U6") (pin "K6") (pinfunction "CIM0_D7/GMAC_RXD7/EPD_PWR3/PB17_K6") (pintype "passive"))
    )
    (net (code "82") (name "unconnected-(U6A-CIM0_HSYN{slash}PB07-PadK7)") (class "Default")
      (node (ref "U6") (pin "K7") (pinfunction "CIM0_HSYN/PB07_K7") (pintype "passive"))
    )
    (net (code "83") (name "unconnected-(U6A-CIM0_MCLK{slash}GMAC_GTXC{slash}EPD_PWC{slash}PB09-PadK2)") (class "Default")
      (node (ref "U6") (pin "K2") (pinfunction "CIM0_MCLK/GMAC_GTXC/EPD_PWC/PB09_K2") (pintype "passive"))
    )
    (net (code "84") (name "unconnected-(U6A-CIM0_PCLK{slash}PB06-PadM1)") (class "Default")
      (node (ref "U6") (pin "M1") (pinfunction "CIM0_PCLK/PB06_M1") (pintype "passive"))
    )
    (net (code "85") (name "unconnected-(U6A-CIM0_VSYN{slash}GMAC_TXER{slash}PB08-PadJ1)") (class "Default")
      (node (ref "U6") (pin "J1") (pinfunction "CIM0_VSYN/GMAC_TXER/PB08_J1") (pintype "passive"))
    )
    (net (code "86") (name "unconnected-(U6A-CIM1_D0{slash}SD8{slash}PG10-PadG2)") (class "Default")
      (node (ref "U6") (pin "G2") (pinfunction "CIM1_D0/SD8/PG10_G2") (pintype "passive"))
    )
    (net (code "87") (name "unconnected-(U6A-CIM1_D2{slash}SD10{slash}PG12-PadE2)") (class "Default")
      (node (ref "U6") (pin "E2") (pinfunction "CIM1_D2/SD10/PG12_E2") (pintype "passive"))
    )
    (net (code "88") (name "unconnected-(U6A-CIM1_D3{slash}SD11{slash}PG13-PadA1)") (class "Default")
      (node (ref "U6") (pin "A1") (pinfunction "CIM1_D3/SD11/PG13_A1") (pintype "passive"))
    )
    (net (code "89") (name "unconnected-(U6A-CIM1_D4{slash}SD12{slash}PG14-PadB1)") (class "Default")
      (node (ref "U6") (pin "B1") (pinfunction "CIM1_D4/SD12/PG14_B1") (pintype "passive"))
    )
    (net (code "90") (name "unconnected-(U6A-CIM1_D5{slash}SD13{slash}PG15-PadD2)") (class "Default")
      (node (ref "U6") (pin "D2") (pinfunction "CIM1_D5/SD13/PG15_D2") (pintype "passive"))
    )
    (net (code "91") (name "unconnected-(U6A-CIM1_D6{slash}SD14{slash}PG16-PadC1)") (class "Default")
      (node (ref "U6") (pin "C1") (pinfunction "CIM1_D6/SD14/PG16_C1") (pintype "passive"))
    )
    (net (code "92") (name "unconnected-(U6A-CIM1_D7{slash}SD15{slash}PG17-PadF2)") (class "Default")
      (node (ref "U6") (pin "F2") (pinfunction "CIM1_D7/SD15/PG17_F2") (pintype "passive"))
    )
    (net (code "93") (name "unconnected-(U6A-CIM1_HSYN{slash}PG07-PadH1)") (class "Default")
      (node (ref "U6") (pin "H1") (pinfunction "CIM1_HSYN/PG07_H1") (pintype "passive"))
    )
    (net (code "94") (name "unconnected-(U6A-CIM1_MCLK{slash}PG09-PadJ2)") (class "Default")
      (node (ref "U6") (pin "J2") (pinfunction "CIM1_MCLK/PG09_J2") (pintype "passive"))
    )
    (net (code "95") (name "unconnected-(U6A-CIM1_PCLK{slash}PG06-PadL3)") (class "Default")
      (node (ref "U6") (pin "L3") (pinfunction "CIM1_PCLK/PG06_L3") (pintype "passive"))
    )
    (net (code "96") (name "unconnected-(U6A-CIM1_VSYN{slash}PG08-PadL4)") (class "Default")
      (node (ref "U6") (pin "L4") (pinfunction "CIM1_VSYN/PG08_L4") (pintype "passive"))
    )
    (net (code "97") (name "unconnected-(U6A-CS2_N{slash}MSC0_D2{slash}PA22-PadB7)") (class "Default")
      (node (ref "U6") (pin "B7") (pinfunction "CS2_N/MSC0_D2/PA22_B7") (pintype "passive"))
    )
    (net (code "98") (name "unconnected-(U6A-CS3_N{slash}MSC0_D3{slash}SSI0_CE0_N{slash}PA23-PadC8)") (class "Default")
      (node (ref "U6") (pin "C8") (pinfunction "CS3_N/MSC0_D3/SSI0_CE0_N/PA23_C8") (pintype "passive"))
    )
    (net (code "99") (name "unconnected-(U6A-DQS_N{slash}PA29-PadB4)") (class "Default")
      (node (ref "U6") (pin "B4") (pinfunction "DQS_N/PA29_B4") (pintype "passive"))
    )
    (net (code "100") (name "unconnected-(U6A-GMAC_MDIO{slash}PCM0_SYN{slash}PF14-PadP1)") (class "Default")
      (node (ref "U6") (pin "P1") (pinfunction "GMAC_MDIO/PCM0_SYN/PF14_P1") (pintype "passive"))
    )
    (net (code "101") (name "unconnected-(U6A-GMAC_RXCLK{slash}PF07-PadV1)") (class "Default")
      (node (ref "U6") (pin "V1") (pinfunction "GMAC_RXCLK/PF07_V1") (pintype "passive"))
    )
    (net (code "102") (name "unconnected-(U6A-GMAC_RXD0{slash}DMIC_CLK{slash}EPD_PWR6{slash}PF10-PadT2)") (class "Default")
      (node (ref "U6") (pin "T2") (pinfunction "GMAC_RXD0/DMIC_CLK/EPD_PWR6/PF10_T2") (pintype "passive"))
    )
    (net (code "103") (name "unconnected-(U6A-GMAC_RXD1{slash}DMIC_IN{slash}EPD_PWR7{slash}PF11-PadR2)") (class "Default")
      (node (ref "U6") (pin "R2") (pinfunction "GMAC_RXD1/DMIC_IN/EPD_PWR7/PF11_R2") (pintype "passive"))
    )
    (net (code "104") (name "unconnected-(U6A-GMAC_RXDV{slash}EPD_PWR5{slash}PF09-PadR3)") (class "Default")
      (node (ref "U6") (pin "R3") (pinfunction "GMAC_RXDV/EPD_PWR5/PF09_R3") (pintype "passive"))
    )
    (net (code "105") (name "unconnected-(U6A-GMAC_RXER{slash}EPD_PWR4{slash}PF08-PadU1)") (class "Default")
      (node (ref "U6") (pin "U1") (pinfunction "GMAC_RXER/EPD_PWR4/PF08_U1") (pintype "passive"))
    )
    (net (code "106") (name "unconnected-(U6A-RD_N{slash}PA16-PadH3)") (class "Default")
      (node (ref "U6") (pin "H3") (pinfunction "RD_N/PA16_H3") (pintype "passive"))
    )
    (net (code "107") (name "unconnected-(U6A-SA2{slash}PB02-PadB3)") (class "Default")
      (node (ref "U6") (pin "B3") (pinfunction "SA2/PB02_B3") (pintype "passive"))
    )
    (net (code "108") (name "unconnected-(U6A-SA3{slash}PB03-PadH2)") (class "Default")
      (node (ref "U6") (pin "H2") (pinfunction "SA3/PB03_H2") (pintype "passive"))
    )
    (net (code "109") (name "unconnected-(U6A-SA4{slash}GMAC_CRS{slash}PB04-PadF1)") (class "Default")
      (node (ref "U6") (pin "F1") (pinfunction "SA4/GMAC_CRS/PB04_F1") (pintype "passive"))
    )
    (net (code "110") (name "unconnected-(U6A-SA5{slash}PB05-PadE1)") (class "Default")
      (node (ref "U6") (pin "E1") (pinfunction "SA5/PB05_E1") (pintype "passive"))
    )
    (net (code "111") (name "unconnected-(U6A-WAIT_N{slash}PA27-PadH4)") (class "Default")
      (node (ref "U6") (pin "H4") (pinfunction "WAIT_N/PA27_H4") (pintype "passive"))
    )
    (net (code "112") (name "unconnected-(U6A-WE_N{slash}PA17-PadG4)") (class "Default")
      (node (ref "U6") (pin "G4") (pinfunction "WE_N/PA17_G4") (pintype "passive"))
    )
    (net (code "113") (name "unconnected-(U6C-ADC_AUX1-PadL20)") (class "Default")
      (node (ref "U6") (pin "L20") (pinfunction "ADC_AUX1_L20") (pintype "passive"))
    )
    (net (code "114") (name "unconnected-(U6C-ADC_AUX2-PadJ21)") (class "Default")
      (node (ref "U6") (pin "J21") (pinfunction "ADC_AUX2_J21") (pintype "passive"))
    )
    (net (code "115") (name "unconnected-(U6C-ADC_XM-PadM19)") (class "Default")
      (node (ref "U6") (pin "M19") (pinfunction "ADC_XM_M19") (pintype "passive"))
    )
    (net (code "116") (name "unconnected-(U6C-ADC_XP-PadK20)") (class "Default")
      (node (ref "U6") (pin "K20") (pinfunction "ADC_XP_K20") (pintype "passive"))
    )
    (net (code "117") (name "unconnected-(U6C-ADC_YM-PadJ20)") (class "Default")
      (node (ref "U6") (pin "J20") (pinfunction "ADC_YM_J20") (pintype "passive"))
    )
    (net (code "118") (name "unconnected-(U6C-ADC_YP-PadM20)") (class "Default")
      (node (ref "U6") (pin "M20") (pinfunction "ADC_YP_M20") (pintype "passive"))
    )
    (net (code "119") (name "unconnected-(U6C-AIL-PadU21)") (class "Default")
      (node (ref "U6") (pin "U21") (pinfunction "AIL_U21") (pintype "passive"))
    )
    (net (code "120") (name "unconnected-(U6C-AIR-PadV21)") (class "Default")
      (node (ref "U6") (pin "V21") (pinfunction "AIR_V21") (pintype "passive"))
    )
    (net (code "121") (name "unconnected-(U6C-AOHPL-PadY18)") (class "Default")
      (node (ref "U6") (pin "Y18") (pinfunction "AOHPL_Y18") (pintype "passive"))
    )
    (net (code "122") (name "unconnected-(U6C-AOHPM-PadW16)") (class "Default")
      (node (ref "U6") (pin "W16") (pinfunction "AOHPM_W16") (pintype "passive"))
    )
    (net (code "123") (name "unconnected-(U6C-AOHPMS-PadW17)") (class "Default")
      (node (ref "U6") (pin "W17") (pinfunction "AOHPMS_W17") (pintype "passive"))
    )
    (net (code "124") (name "unconnected-(U6C-AOHPR-PadAA18)") (class "Default")
      (node (ref "U6") (pin "AA18") (pinfunction "AOHPR_AA18") (pintype "passive"))
    )
    (net (code "125") (name "unconnected-(U6C-AOLON-PadY16)") (class "Default")
      (node (ref "U6") (pin "Y16") (pinfunction "AOLON_Y16") (pintype "passive"))
    )
    (net (code "126") (name "unconnected-(U6C-AOLOP-PadY17)") (class "Default")
      (node (ref "U6") (pin "Y17") (pinfunction "AOLOP_Y17") (pintype "passive"))
    )
    (net (code "127") (name "unconnected-(U6C-HPSENSE-PadY19)") (class "Default")
      (node (ref "U6") (pin "Y19") (pinfunction "HPSENSE_Y19") (pintype "passive"))
    )
    (net (code "128") (name "unconnected-(U6C-MICBIAS-PadY21)") (class "Default")
      (node (ref "U6") (pin "Y21") (pinfunction "MICBIAS_Y21") (pintype "passive"))
    )
    (net (code "129") (name "unconnected-(U6C-MICN1-PadV20)") (class "Default")
      (node (ref "U6") (pin "V20") (pinfunction "MICN1_V20") (pintype "passive"))
    )
    (net (code "130") (name "unconnected-(U6C-MICP1-PadW20)") (class "Default")
      (node (ref "U6") (pin "W20") (pinfunction "MICP1_W20") (pintype "passive"))
    )
    (net (code "131") (name "unconnected-(U6C-TEST_TE-PadR10)") (class "Default")
      (node (ref "U6") (pin "R10") (pinfunction "TEST_TE_R10") (pintype "passive"))
    )
    (net (code "132") (name "unconnected-(U6C-UHC_DM1-PadV13)") (class "Default")
      (node (ref "U6") (pin "V13") (pinfunction "UHC_DM1_V13") (pintype "passive"))
    )
    (net (code "133") (name "unconnected-(U6C-UHC_DP1-PadW13)") (class "Default")
      (node (ref "U6") (pin "W13") (pinfunction "UHC_DP1_W13") (pintype "passive"))
    )
    (net (code "134") (name "unconnected-(U6D-VDDIO2-PadN8)") (class "Default")
      (node (ref "U6") (pin "N8") (pinfunction "VDDIO2_N8") (pintype "passive"))
    )
    (net (code "135") (name "unconnected-(U6D-VDDIO3-PadP8)") (class "Default")
      (node (ref "U6") (pin "P8") (pinfunction "VDDIO3_P8") (pintype "passive"))
    )
    (net (code "136") (name "unconnected-(U6D-VDDIO4-PadP9)") (class "Default")
      (node (ref "U6") (pin "P9") (pinfunction "VDDIO4_P9") (pintype "passive"))
    )
  )
)
